# RJ45_Sheet.net
KiCad netlist of a schematic drawn in Altium Designer
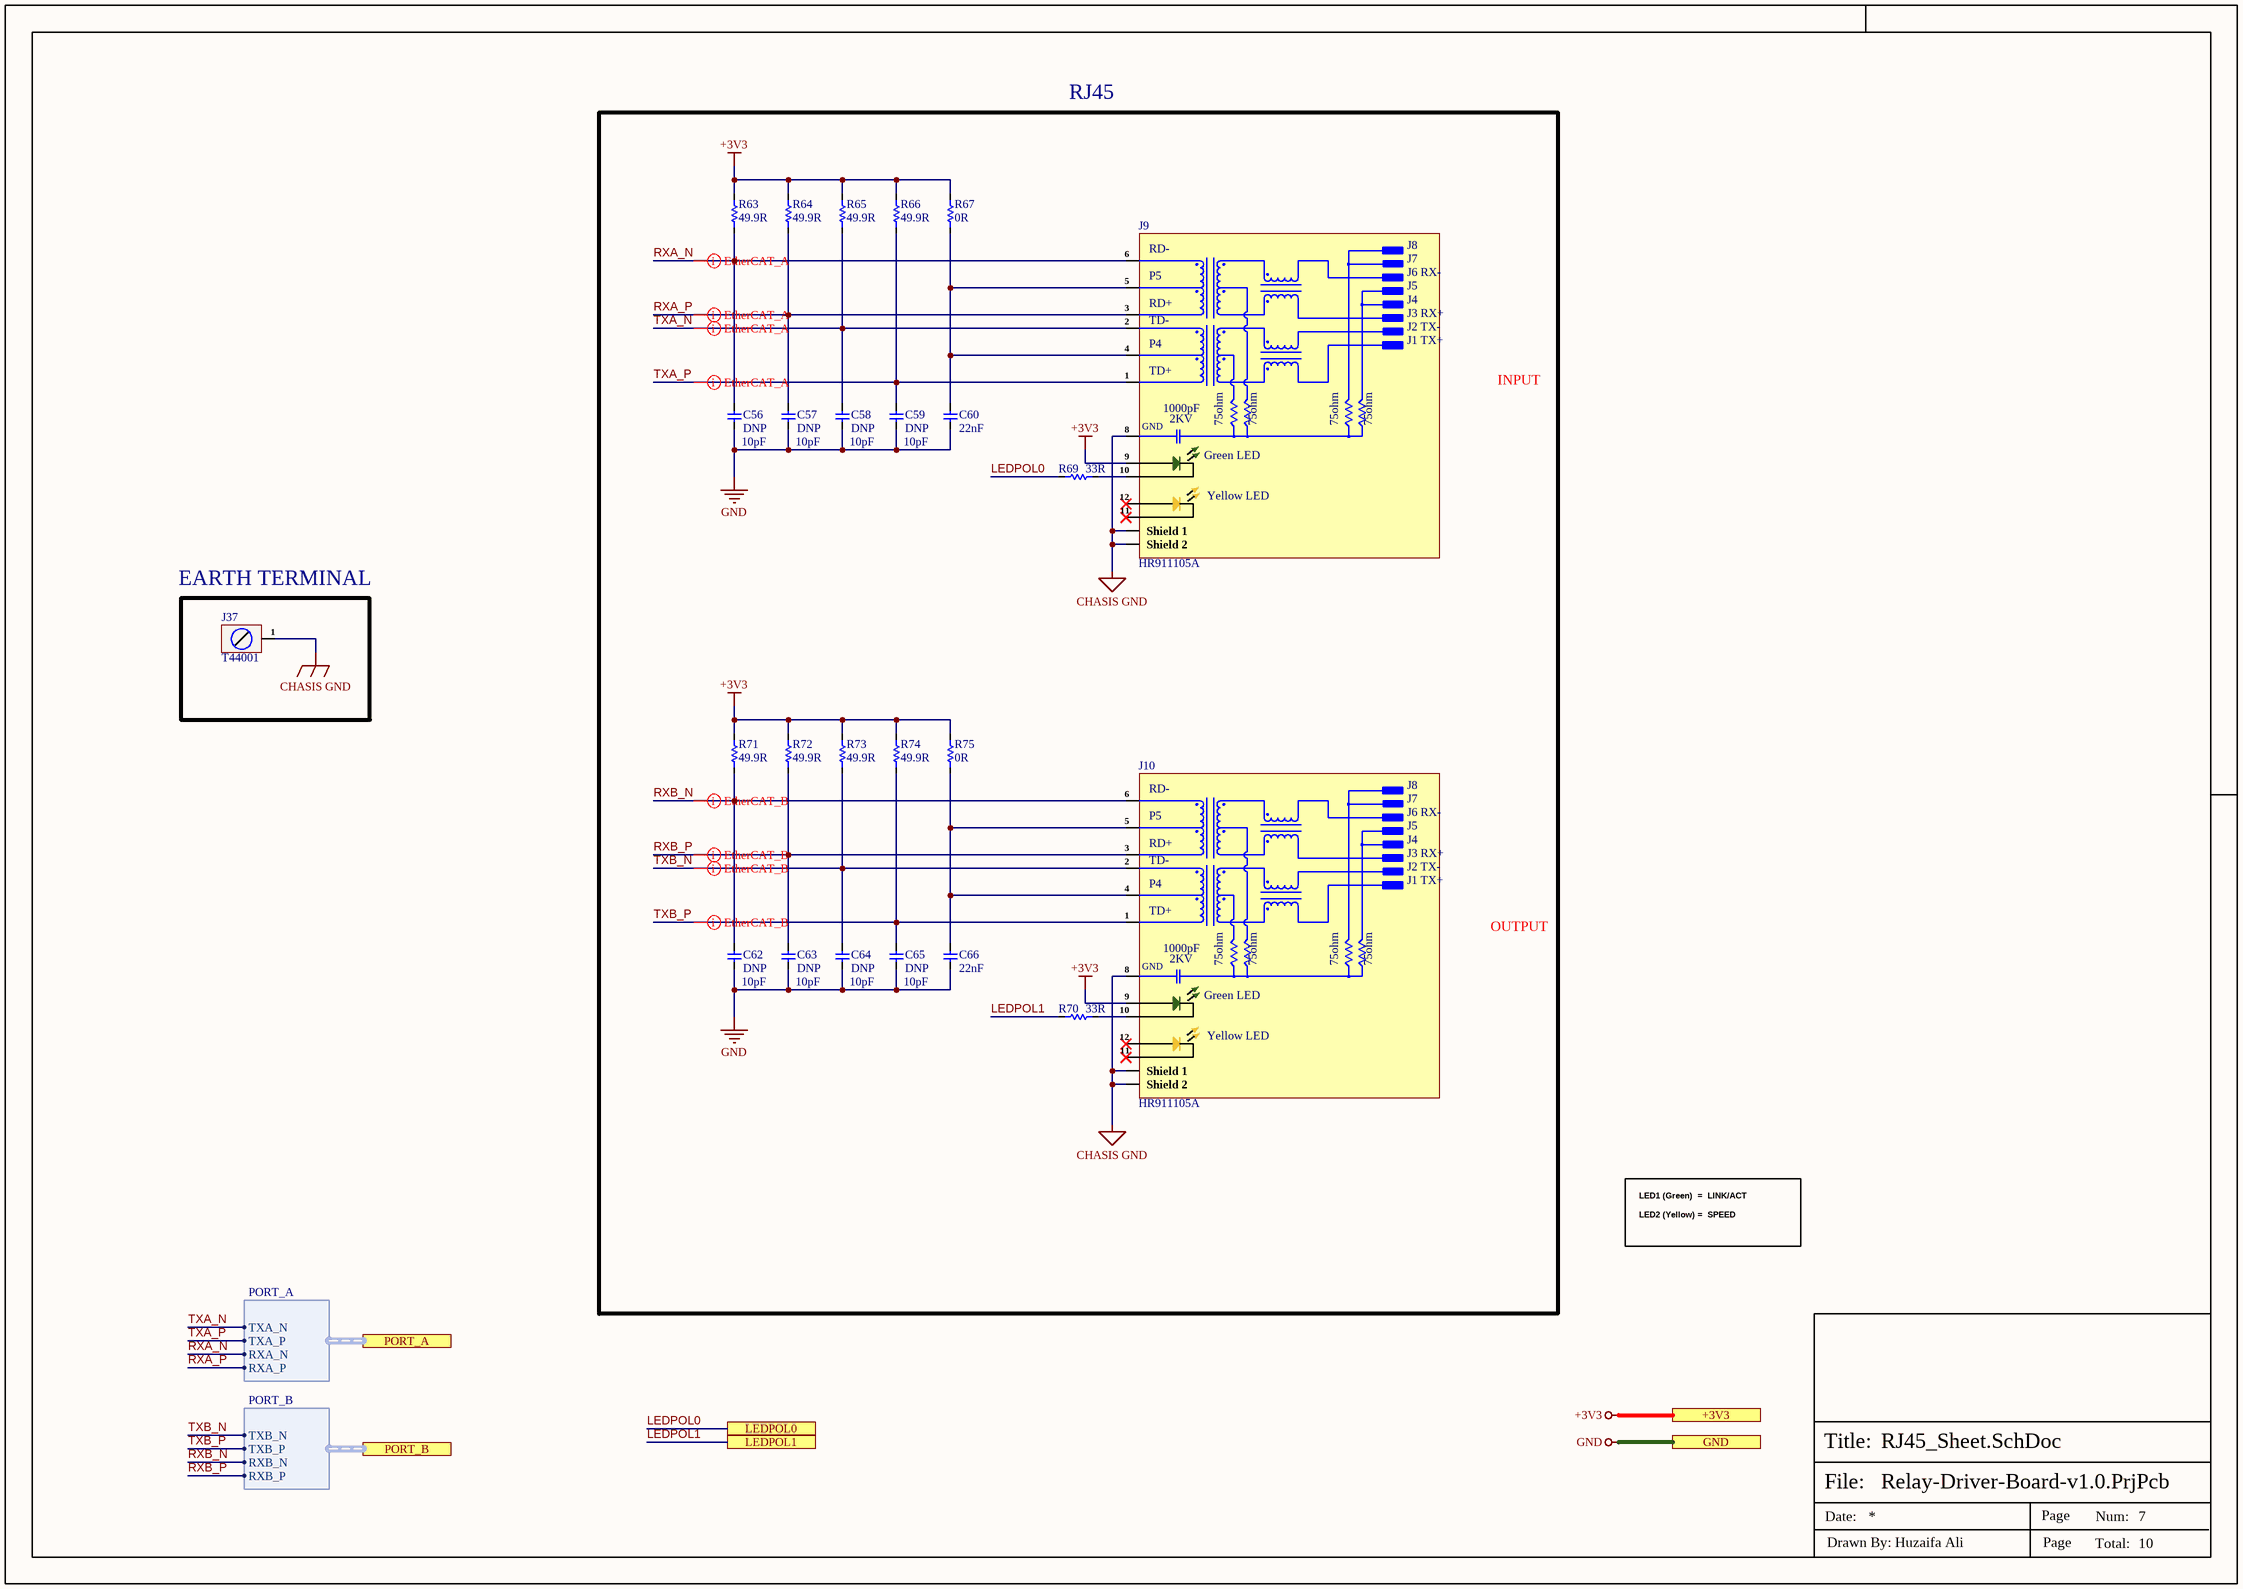
[diagram p0: RJ45_Sheet.SchDoc]

(export (version "E")
  (design (tool "Eeschema 10.0.6"))
  (components
    (comp (ref "C56")
      (value "DNP")
      (footprint "Cap-0402")
      (description "CAP CER 10PF 50V C0G/NP0 0402")
      (fields
        (field (name "MANUFACTURER") "Murata")
        (field (name "MANUFACTURER PART NUMBER") "GRM1555C1H100JA01D")
      )
      (libsource (lib "eSpark Libraries") (part "GRM1555C1H100JA01D"))
    )
    (comp (ref "C57")
      (value "DNP")
      (footprint "Cap-0402")
      (description "CAP CER 10PF 50V C0G/NP0 0402")
      (fields
        (field (name "MANUFACTURER") "Murata")
        (field (name "MANUFACTURER PART NUMBER") "GRM1555C1H100JA01D")
      )
      (libsource (lib "eSpark Libraries") (part "GRM1555C1H100JA01D"))
    )
    (comp (ref "C58")
      (value "DNP")
      (footprint "Cap-0402")
      (description "CAP CER 10PF 50V C0G/NP0 0402")
      (fields
        (field (name "MANUFACTURER") "Murata")
        (field (name "MANUFACTURER PART NUMBER") "GRM1555C1H100JA01D")
      )
      (libsource (lib "eSpark Libraries") (part "GRM1555C1H100JA01D"))
    )
    (comp (ref "C59")
      (value "DNP")
      (footprint "Cap-0402")
      (description "CAP CER 10PF 50V C0G/NP0 0402")
      (fields
        (field (name "MANUFACTURER") "Murata")
        (field (name "MANUFACTURER PART NUMBER") "GRM1555C1H100JA01D")
      )
      (libsource (lib "eSpark Libraries") (part "GRM1555C1H100JA01D"))
    )
    (comp (ref "C60")
      (value "22nF")
      (footprint "Cap-0402")
      (description "CAP CER 0.022UF 16V X7R 0402")
      (fields
        (field (name "MANUFACTURER") "Yageo")
        (field (name "MANUFACTURER PART NUMBER") "CC0402JRX7R7BB223")
      )
      (libsource (lib "eSpark Libraries") (part "CC0402JRX7R7BB223"))
    )
    (comp (ref "C62")
      (value "DNP")
      (footprint "Cap-0402")
      (description "CAP CER 10PF 50V C0G/NP0 0402")
      (fields
        (field (name "MANUFACTURER") "Murata")
        (field (name "MANUFACTURER PART NUMBER") "GRM1555C1H100JA01D")
      )
      (libsource (lib "eSpark Libraries") (part "GRM1555C1H100JA01D"))
    )
    (comp (ref "C63")
      (value "DNP")
      (footprint "Cap-0402")
      (description "CAP CER 10PF 50V C0G/NP0 0402")
      (fields
        (field (name "MANUFACTURER") "Murata")
        (field (name "MANUFACTURER PART NUMBER") "GRM1555C1H100JA01D")
      )
      (libsource (lib "eSpark Libraries") (part "GRM1555C1H100JA01D"))
    )
    (comp (ref "C64")
      (value "DNP")
      (footprint "Cap-0402")
      (description "CAP CER 10PF 50V C0G/NP0 0402")
      (fields
        (field (name "MANUFACTURER") "Murata")
        (field (name "MANUFACTURER PART NUMBER") "GRM1555C1H100JA01D")
      )
      (libsource (lib "eSpark Libraries") (part "GRM1555C1H100JA01D"))
    )
    (comp (ref "C65")
      (value "DNP")
      (footprint "Cap-0402")
      (description "CAP CER 10PF 50V C0G/NP0 0402")
      (fields
        (field (name "MANUFACTURER") "Murata")
        (field (name "MANUFACTURER PART NUMBER") "GRM1555C1H100JA01D")
      )
      (libsource (lib "eSpark Libraries") (part "GRM1555C1H100JA01D"))
    )
    (comp (ref "C66")
      (value "22nF")
      (footprint "Cap-0402")
      (description "CAP CER 0.022UF 16V X7R 0402")
      (fields
        (field (name "MANUFACTURER") "Yageo")
        (field (name "MANUFACTURER PART NUMBER") "CC0402JRX7R7BB223")
      )
      (libsource (lib "eSpark Libraries") (part "CC0402JRX7R7BB223"))
    )
    (comp (ref "J9")
      (value "HR911105A")
      (footprint "HR911105A")
      (description "RJ45 RJReceptacle 1 WithLED Plugin Ethernet Connectors/Modular Connectors (RJ45 RJ11) ROHS")
      (fields (field (name "MANUFACTURER") "HANRUN") (field (name "LCSC PART NUMBER") "C12074"))
      (libsource (lib "eSpark Libraries") (part "HR911105A"))
    )
    (comp (ref "J10")
      (value "HR911105A")
      (footprint "HR911105A")
      (description "RJ45 RJReceptacle 1 WithLED Plugin Ethernet Connectors/Modular Connectors (RJ45 RJ11) ROHS")
      (fields (field (name "MANUFACTURER") "HANRUN") (field (name "LCSC PART NUMBER") "C12074"))
      (libsource (lib "eSpark Libraries") (part "HR911105A"))
    )
    (comp (ref "J37")
      (value "T44001")
      (footprint "T44001")
      (description "M4 Plugin PCB Welding Terminal ROHS")
      (fields (field (name "MANUFACTURER") "XFCN"))
      (libsource (lib "eSpark Libraries") (part "T44001"))
    )
    (comp (ref "R63")
      (value "49.9R")
      (footprint "Res-0603")
      (description "RES 49.9 OHM 1% 1/10W 0603")
      (fields
        (field (name "MANUFACTURER") "Yageo")
        (field (name "MANUFACTURER PART NUMBER") "RC0603FR-0749R9L")
      )
      (libsource (lib "eSpark Libraries") (part "RC0603FR-0749R9L"))
    )
    (comp (ref "R64")
      (value "49.9R")
      (footprint "Res-0603")
      (description "RES 49.9 OHM 1% 1/10W 0603")
      (fields
        (field (name "MANUFACTURER") "Yageo")
        (field (name "MANUFACTURER PART NUMBER") "RC0603FR-0749R9L")
      )
      (libsource (lib "eSpark Libraries") (part "RC0603FR-0749R9L"))
    )
    (comp (ref "R65")
      (value "49.9R")
      (footprint "Res-0603")
      (description "RES 49.9 OHM 1% 1/10W 0603")
      (fields
        (field (name "MANUFACTURER") "Yageo")
        (field (name "MANUFACTURER PART NUMBER") "RC0603FR-0749R9L")
      )
      (libsource (lib "eSpark Libraries") (part "RC0603FR-0749R9L"))
    )
    (comp (ref "R66")
      (value "49.9R")
      (footprint "Res-0603")
      (description "RES 49.9 OHM 1% 1/10W 0603")
      (fields
        (field (name "MANUFACTURER") "Yageo")
        (field (name "MANUFACTURER PART NUMBER") "RC0603FR-0749R9L")
      )
      (libsource (lib "eSpark Libraries") (part "RC0603FR-0749R9L"))
    )
    (comp (ref "R67")
      (value "0R")
      (footprint "Res-0402")
      (description "RESISTOR 0402 JUMPER ZERO OHM")
      (fields
        (field (name "MANUFACTURER") "Yageo")
        (field (name "MANUFACTURER PART NUMBER") "AC0402FR-070RL")
      )
      (libsource (lib "eSpark Libraries") (part "AC0402FR-070RL"))
    )
    (comp (ref "R69")
      (value "33R")
      (footprint "Res-0402")
      (description "RES 33 OHM 1% 1/16W 0402")
      (fields
        (field (name "MANUFACTURER") "Yageo")
        (field (name "MANUFACTURER PART NUMBER") "RC0402FR-0733RL")
      )
      (libsource (lib "eSpark Libraries") (part "RC0402FR-0733RL"))
    )
    (comp (ref "R70")
      (value "33R")
      (footprint "Res-0402")
      (description "RES 33 OHM 1% 1/16W 0402")
      (fields
        (field (name "MANUFACTURER") "Yageo")
        (field (name "MANUFACTURER PART NUMBER") "RC0402FR-0733RL")
      )
      (libsource (lib "eSpark Libraries") (part "RC0402FR-0733RL"))
    )
    (comp (ref "R71")
      (value "49.9R")
      (footprint "Res-0603")
      (description "RES 49.9 OHM 1% 1/10W 0603")
      (fields
        (field (name "MANUFACTURER") "Yageo")
        (field (name "MANUFACTURER PART NUMBER") "RC0603FR-0749R9L")
      )
      (libsource (lib "eSpark Libraries") (part "RC0603FR-0749R9L"))
    )
    (comp (ref "R72")
      (value "49.9R")
      (footprint "Res-0603")
      (description "RES 49.9 OHM 1% 1/10W 0603")
      (fields
        (field (name "MANUFACTURER") "Yageo")
        (field (name "MANUFACTURER PART NUMBER") "RC0603FR-0749R9L")
      )
      (libsource (lib "eSpark Libraries") (part "RC0603FR-0749R9L"))
    )
    (comp (ref "R73")
      (value "49.9R")
      (footprint "Res-0603")
      (description "RES 49.9 OHM 1% 1/10W 0603")
      (fields
        (field (name "MANUFACTURER") "Yageo")
        (field (name "MANUFACTURER PART NUMBER") "RC0603FR-0749R9L")
      )
      (libsource (lib "eSpark Libraries") (part "RC0603FR-0749R9L"))
    )
    (comp (ref "R74")
      (value "49.9R")
      (footprint "Res-0603")
      (description "RES 49.9 OHM 1% 1/10W 0603")
      (fields
        (field (name "MANUFACTURER") "Yageo")
        (field (name "MANUFACTURER PART NUMBER") "RC0603FR-0749R9L")
      )
      (libsource (lib "eSpark Libraries") (part "RC0603FR-0749R9L"))
    )
    (comp (ref "R75")
      (value "0R")
      (footprint "Res-0402")
      (description "RESISTOR 0402 JUMPER ZERO OHM")
      (fields
        (field (name "MANUFACTURER") "Yageo")
        (field (name "MANUFACTURER PART NUMBER") "AC0402FR-070RL")
      )
      (libsource (lib "eSpark Libraries") (part "AC0402FR-070RL"))
    )
  )
  (nets
    (net (code "3") (name "+3V3") (class "Default")
      (node (ref "J10") (pin "9") (pinfunction "ANODE_9") (pintype "passive"))
      (node (ref "J9") (pin "9") (pinfunction "ANODE_9") (pintype "passive"))
      (node (ref "R63") (pin "2") (pinfunction "2_2") (pintype "passive"))
      (node (ref "R64") (pin "2") (pinfunction "2_2") (pintype "passive"))
      (node (ref "R65") (pin "2") (pinfunction "2_2") (pintype "passive"))
      (node (ref "R66") (pin "2") (pinfunction "2_2") (pintype "passive"))
      (node (ref "R67") (pin "2") (pinfunction "2_2") (pintype "passive"))
      (node (ref "R71") (pin "2") (pinfunction "2_2") (pintype "passive"))
      (node (ref "R72") (pin "2") (pinfunction "2_2") (pintype "passive"))
      (node (ref "R73") (pin "2") (pinfunction "2_2") (pintype "passive"))
      (node (ref "R74") (pin "2") (pinfunction "2_2") (pintype "passive"))
      (node (ref "R75") (pin "2") (pinfunction "2_2") (pintype "passive"))
    )
    (net (code "4") (name "/LEDPOL0") (class "Default")
      (node (ref "R69") (pin "1") (pinfunction "1_1") (pintype "passive"))
    )
    (net (code "5") (name "/LEDPOL1") (class "Default")
      (node (ref "R70") (pin "1") (pinfunction "1_1") (pintype "passive"))
    )
    (net (code "6") (name "/RXA_N") (class "Default")
      (node (ref "C56") (pin "2") (pinfunction "2_2") (pintype "passive"))
      (node (ref "J9") (pin "6") (pinfunction "RD-_6") (pintype "passive"))
      (node (ref "R63") (pin "1") (pinfunction "1_1") (pintype "passive"))
    )
    (net (code "7") (name "/RXA_P") (class "Default")
      (node (ref "C57") (pin "2") (pinfunction "2_2") (pintype "passive"))
      (node (ref "J9") (pin "3") (pinfunction "RD+_3") (pintype "passive"))
      (node (ref "R64") (pin "1") (pinfunction "1_1") (pintype "passive"))
    )
    (net (code "8") (name "/RXB_N") (class "Default")
      (node (ref "C62") (pin "2") (pinfunction "2_2") (pintype "passive"))
      (node (ref "J10") (pin "6") (pinfunction "RD-_6") (pintype "passive"))
      (node (ref "R71") (pin "1") (pinfunction "1_1") (pintype "passive"))
    )
    (net (code "9") (name "/RXB_P") (class "Default")
      (node (ref "C63") (pin "2") (pinfunction "2_2") (pintype "passive"))
      (node (ref "J10") (pin "3") (pinfunction "RD+_3") (pintype "passive"))
      (node (ref "R72") (pin "1") (pinfunction "1_1") (pintype "passive"))
    )
    (net (code "10") (name "/TXA_N") (class "Default")
      (node (ref "C58") (pin "2") (pinfunction "2_2") (pintype "passive"))
      (node (ref "J9") (pin "2") (pinfunction "TD-_2") (pintype "passive"))
      (node (ref "R65") (pin "1") (pinfunction "1_1") (pintype "passive"))
    )
    (net (code "11") (name "/TXA_P") (class "Default")
      (node (ref "C59") (pin "2") (pinfunction "2_2") (pintype "passive"))
      (node (ref "J9") (pin "1") (pinfunction "TD+_1") (pintype "passive"))
      (node (ref "R66") (pin "1") (pinfunction "1_1") (pintype "passive"))
    )
    (net (code "12") (name "/TXB_N") (class "Default")
      (node (ref "C64") (pin "2") (pinfunction "2_2") (pintype "passive"))
      (node (ref "J10") (pin "2") (pinfunction "TD-_2") (pintype "passive"))
      (node (ref "R73") (pin "1") (pinfunction "1_1") (pintype "passive"))
    )
    (net (code "13") (name "/TXB_P") (class "Default")
      (node (ref "C65") (pin "2") (pinfunction "2_2") (pintype "passive"))
      (node (ref "J10") (pin "1") (pinfunction "TD+_1") (pintype "passive"))
      (node (ref "R74") (pin "1") (pinfunction "1_1") (pintype "passive"))
    )
    (net (code "16") (name "CHASIS GND") (class "Default")
      (node (ref "J10") (pin "8") (pinfunction "GND_8") (pintype "power_in"))
      (node (ref "J10") (pin "Shield_1") (pinfunction "Shield_1_Shield_1") (pintype "passive"))
      (node (ref "J10") (pin "Shield_2") (pinfunction "Shield_2_Shield_2") (pintype "passive"))
      (node (ref "J37") (pin "1") (pinfunction "1_1") (pintype "passive"))
      (node (ref "J9") (pin "8") (pinfunction "GND_8") (pintype "power_in"))
      (node (ref "J9") (pin "Shield_1") (pinfunction "Shield_1_Shield_1") (pintype "passive"))
      (node (ref "J9") (pin "Shield_2") (pinfunction "Shield_2_Shield_2") (pintype "passive"))
    )
    (net (code "17") (name "GND") (class "Default")
      (node (ref "C56") (pin "1") (pinfunction "1_1") (pintype "passive"))
      (node (ref "C57") (pin "1") (pinfunction "1_1") (pintype "passive"))
      (node (ref "C58") (pin "1") (pinfunction "1_1") (pintype "passive"))
      (node (ref "C59") (pin "1") (pinfunction "1_1") (pintype "passive"))
      (node (ref "C60") (pin "1") (pinfunction "1_1") (pintype "passive"))
      (node (ref "C62") (pin "1") (pinfunction "1_1") (pintype "passive"))
      (node (ref "C63") (pin "1") (pinfunction "1_1") (pintype "passive"))
      (node (ref "C64") (pin "1") (pinfunction "1_1") (pintype "passive"))
      (node (ref "C65") (pin "1") (pinfunction "1_1") (pintype "passive"))
      (node (ref "C66") (pin "1") (pinfunction "1_1") (pintype "passive"))
    )
    (net (code "18") (name "Net-(J9-CATHODE-Pad10)") (class "Default")
      (node (ref "J9") (pin "10") (pinfunction "CATHODE_10") (pintype "passive"))
      (node (ref "R69") (pin "2") (pinfunction "2_2") (pintype "passive"))
    )
    (net (code "19") (name "Net-(J9-P4)") (class "Default")
      (node (ref "C60") (pin "2") (pinfunction "2_2") (pintype "passive"))
      (node (ref "J9") (pin "4") (pinfunction "P4_4") (pintype "passive"))
      (node (ref "J9") (pin "5") (pinfunction "P5_5") (pintype "passive"))
      (node (ref "R67") (pin "1") (pinfunction "1_1") (pintype "passive"))
    )
    (net (code "20") (name "Net-(J10-CATHODE-Pad10)") (class "Default")
      (node (ref "J10") (pin "10") (pinfunction "CATHODE_10") (pintype "passive"))
      (node (ref "R70") (pin "2") (pinfunction "2_2") (pintype "passive"))
    )
    (net (code "21") (name "Net-(J10-P4)") (class "Default")
      (node (ref "C66") (pin "2") (pinfunction "2_2") (pintype "passive"))
      (node (ref "J10") (pin "4") (pinfunction "P4_4") (pintype "passive"))
      (node (ref "J10") (pin "5") (pinfunction "P5_5") (pintype "passive"))
      (node (ref "R75") (pin "1") (pinfunction "1_1") (pintype "passive"))
    )
    (net (code "22") (name "unconnected-(J9-ANODE-Pad12)") (class "Default")
      (node (ref "J9") (pin "12") (pinfunction "ANODE_12") (pintype "passive+no_connect"))
    )
    (net (code "23") (name "unconnected-(J9-CATHODE-Pad11)") (class "Default")
      (node (ref "J9") (pin "11") (pinfunction "CATHODE_11") (pintype "passive+no_connect"))
    )
    (net (code "24") (name "unconnected-(J10-ANODE-Pad12)") (class "Default")
      (node (ref "J10") (pin "12") (pinfunction "ANODE_12") (pintype "passive+no_connect"))
    )
    (net (code "25") (name "unconnected-(J10-CATHODE-Pad11)") (class "Default")
      (node (ref "J10") (pin "11") (pinfunction "CATHODE_11") (pintype "passive+no_connect"))
    )
  )
)
